# clock-delay.net
KiCad netlist of a schematic drawn in EAGLE
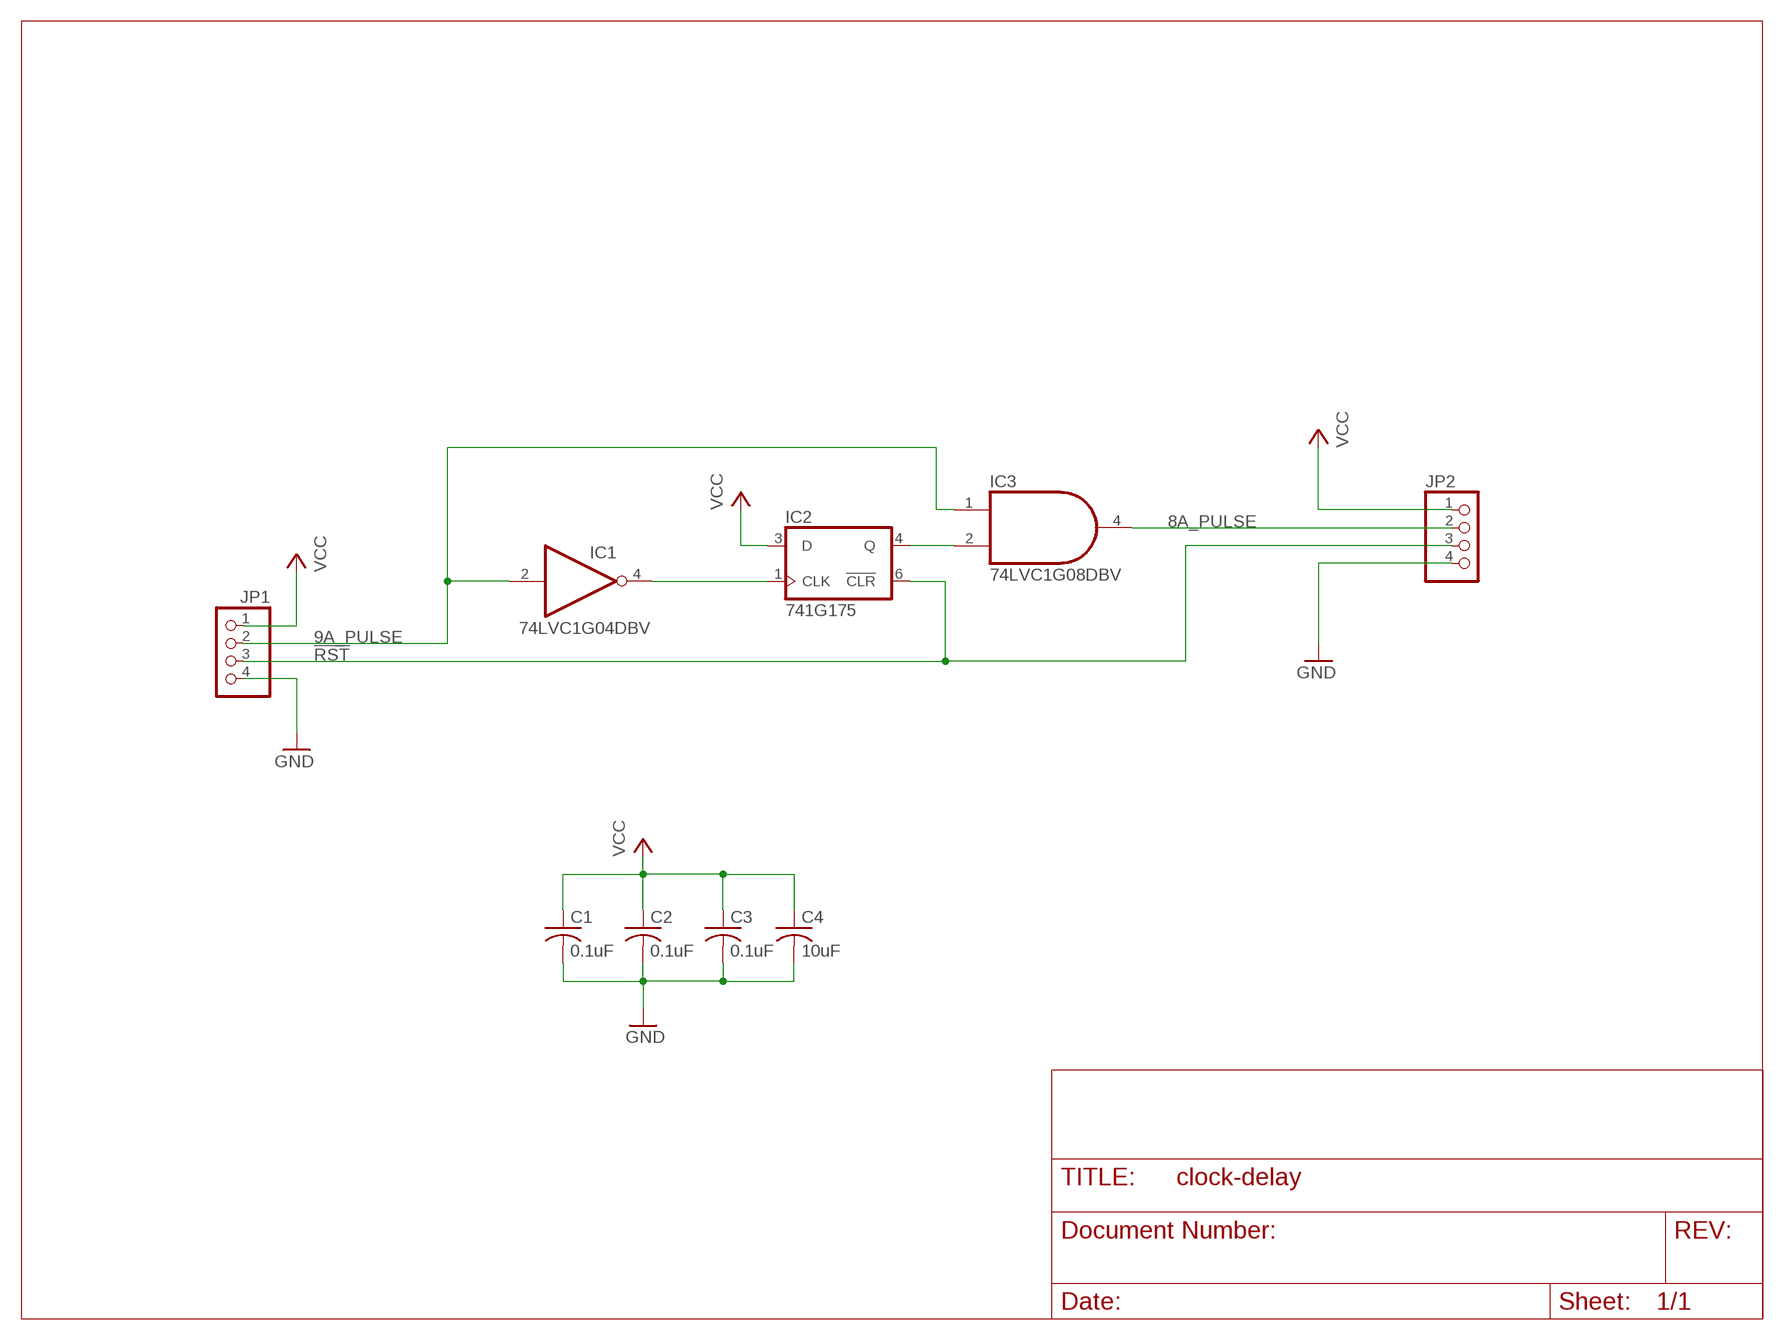
[diagram p0: schematic, sheet 1]

(export (version "E")
  (design (tool "Eeschema 10.0.6"))
  (components
    (comp (ref "C1")
      (value "0.1uF")
      (footprint "eagle-import:C0805")
      (libsource (lib "eagle-import") (part "C-USC0805"))
    )
    (comp (ref "C2")
      (value "0.1uF")
      (footprint "eagle-import:C0805")
      (libsource (lib "eagle-import") (part "C-USC0805"))
    )
    (comp (ref "C3")
      (value "0.1uF")
      (footprint "eagle-import:C0805")
      (libsource (lib "eagle-import") (part "C-USC0805"))
    )
    (comp (ref "C4")
      (value "10uF")
      (footprint "eagle-import:C0805")
      (libsource (lib "eagle-import") (part "C-USC0805"))
    )
    (comp (ref "IC1")
      (value "74LVC1G04DBV")
      (footprint "eagle-import:SOT23-5")
      (libsource (lib "eagle-import") (part "741G04DBVLVC"))
    )
    (comp (ref "IC2")
      (value "741G175")
      (footprint "eagle-import:DBV_R-PDSO-G6")
      (libsource (lib "eagle-import") (part "741G175"))
    )
    (comp (ref "IC3")
      (value "74LVC1G08DBV")
      (footprint "eagle-import:SOT23-5")
      (libsource (lib "eagle-import") (part "741G08DBVLVC"))
    )
    (comp (ref "JP1")
      (value "PINHD-1X4")
      (footprint "eagle-import:1X04")
      (libsource (lib "eagle-import") (part "PINHD-1X4"))
    )
    (comp (ref "JP2")
      (value "PINHD-1X4")
      (footprint "eagle-import:1X04")
      (libsource (lib "eagle-import") (part "PINHD-1X4"))
    )
  )
  (nets
    (net (code "1") (name "/8A_PULSE") (class "Default")
      (node (ref "IC3") (pin "4") (pinfunction "O_4") (pintype "output"))
      (node (ref "JP2") (pin "2") (pinfunction "2_2") (pintype "passive"))
    )
    (net (code "2") (name "/9A_PULSE") (class "Default")
      (node (ref "IC1") (pin "2") (pinfunction "I_2") (pintype "input"))
      (node (ref "IC3") (pin "1") (pinfunction "I0_1") (pintype "input"))
      (node (ref "JP1") (pin "2") (pinfunction "2_2") (pintype "passive"))
    )
    (net (code "3") (name "/~{RST}") (class "Default")
      (node (ref "IC2") (pin "6") (pinfunction "~{CLR}_6") (pintype "input"))
      (node (ref "JP1") (pin "3") (pinfunction "3_3") (pintype "passive"))
      (node (ref "JP2") (pin "3") (pinfunction "3_3") (pintype "passive"))
    )
    (net (code "4") (name "GND") (class "Default")
      (node (ref "C1") (pin "2") (pinfunction "2_2") (pintype "passive"))
      (node (ref "C2") (pin "2") (pinfunction "2_2") (pintype "passive"))
      (node (ref "C3") (pin "2") (pinfunction "2_2") (pintype "passive"))
      (node (ref "C4") (pin "2") (pinfunction "2_2") (pintype "passive"))
      (node (ref "JP1") (pin "4") (pinfunction "4_4") (pintype "passive"))
      (node (ref "JP2") (pin "4") (pinfunction "4_4") (pintype "passive"))
    )
    (net (code "5") (name "Net-(IC1A-O)") (class "Default")
      (node (ref "IC1") (pin "4") (pinfunction "O_4") (pintype "output"))
      (node (ref "IC2") (pin "1") (pinfunction "CLK_1") (pintype "input"))
    )
    (net (code "6") (name "Net-(IC2A-Q)") (class "Default")
      (node (ref "IC2") (pin "4") (pinfunction "Q_4") (pintype "output"))
      (node (ref "IC3") (pin "2") (pinfunction "I1_2") (pintype "input"))
    )
    (net (code "7") (name "VCC") (class "Default")
      (node (ref "C1") (pin "1") (pinfunction "1_1") (pintype "passive"))
      (node (ref "C2") (pin "1") (pinfunction "1_1") (pintype "passive"))
      (node (ref "C3") (pin "1") (pinfunction "1_1") (pintype "passive"))
      (node (ref "C4") (pin "1") (pinfunction "1_1") (pintype "passive"))
      (node (ref "IC2") (pin "3") (pinfunction "D_3") (pintype "input"))
      (node (ref "JP1") (pin "1") (pinfunction "1_1") (pintype "passive"))
      (node (ref "JP2") (pin "1") (pinfunction "1_1") (pintype "passive"))
    )
  )
)
